# xds100v2.net
KiCad netlist of a schematic drawn in Altium Designer
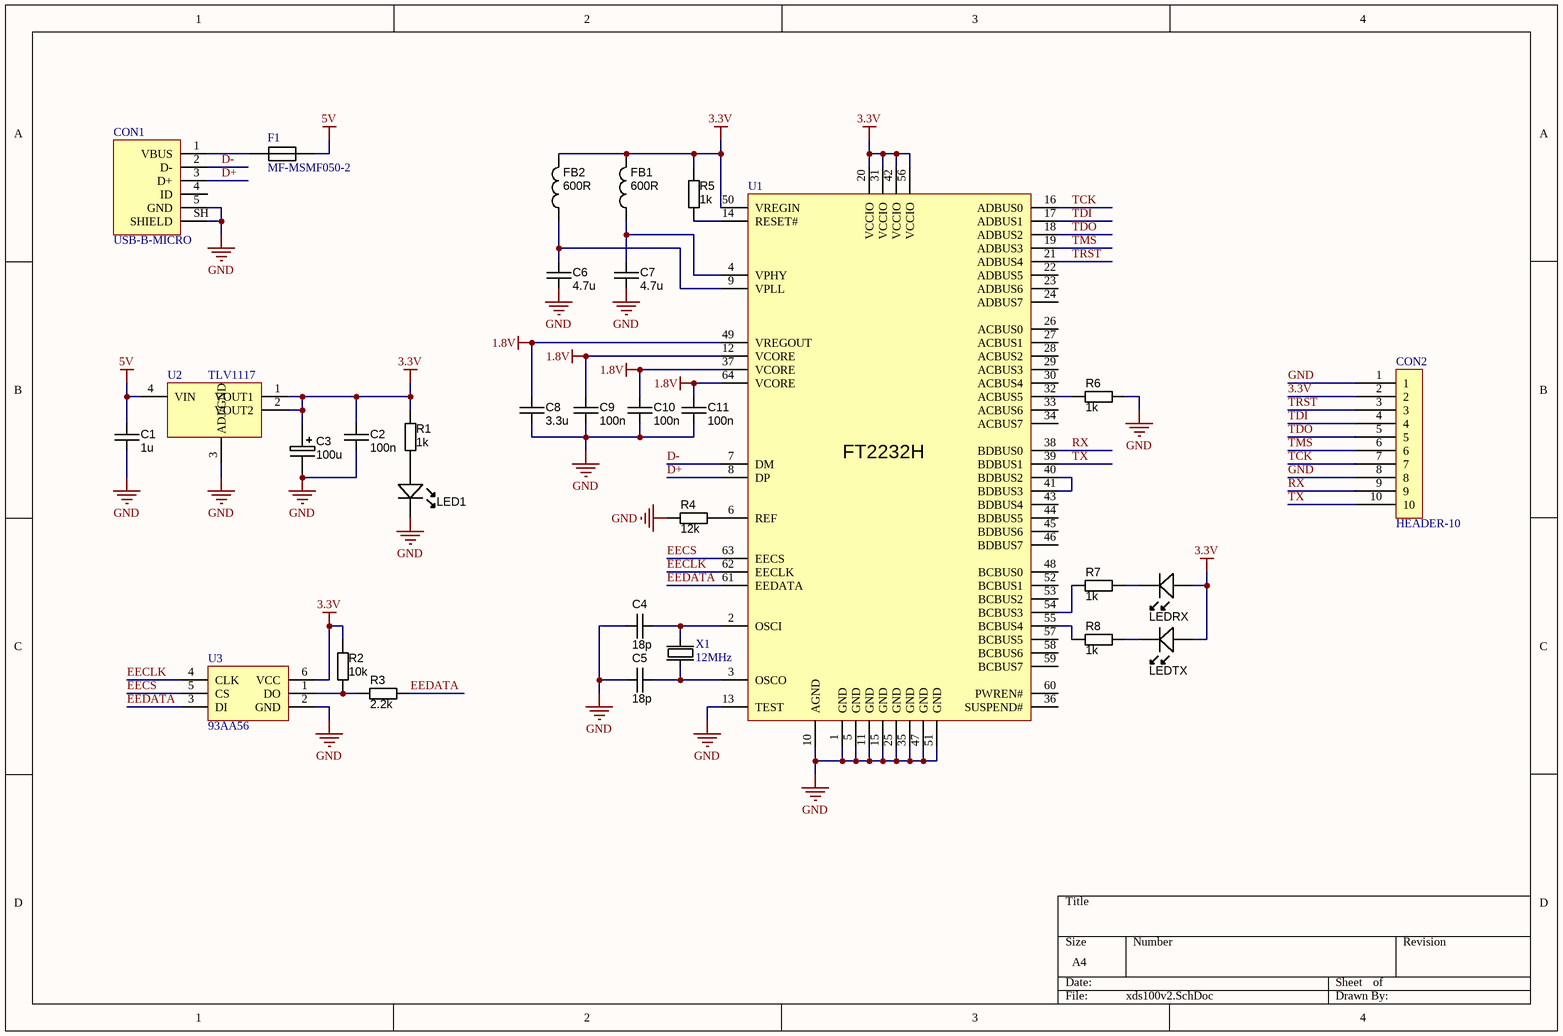
[diagram p0: xds100v2.SchDoc]

(export (version "E")
  (design (tool "Eeschema 10.0.6"))
  (components
    (comp (ref "C1")
      (value "1u")
      (footprint "CAPC1608X90N")
      (description "Capacitor SMD Cer 1uF 10% 16V X7R 0603")
      (fields (field (name "TOLERANCE") "±10%"))
      (libsource (lib "PBL - Capacitors") (part "CAPC_1u_0603_X7R_16V_10%"))
    )
    (comp (ref "C2")
      (value "100n")
      (footprint "CAPC1608X90N")
      (description "Capacitor SMD Cer 1uF 10% 16V X7R 0603")
      (fields (field (name "TOLERANCE") "±10%"))
      (libsource (lib "PBL - Capacitors") (part "CAPC_1u_0603_X7R_16V_10%"))
    )
    (comp (ref "C3")
      (value "100u")
      (footprint "CAPMP3528X210N")
      (description "Capacitor SMD Tantalum 100uF 20% 6.3V 1210")
      (fields (field (name "TOLERANCE") "±20%"))
      (libsource (lib "PBL - Capacitors") (part "CAPT_100u_1210_6V3"))
    )
    (comp (ref "C4")
      (value "18p")
      (footprint "CAPC1608X90N")
      (description "Capacitor SMD Cer 1uF 10% 16V X7R 0603")
      (fields (field (name "TOLERANCE") "±10%"))
      (libsource (lib "PBL - Capacitors") (part "CAPC_1u_0603_X7R_16V_10%"))
    )
    (comp (ref "C5")
      (value "18p")
      (footprint "CAPC1608X90N")
      (description "Capacitor SMD Cer 1uF 10% 16V X7R 0603")
      (fields (field (name "TOLERANCE") "±10%"))
      (libsource (lib "PBL - Capacitors") (part "CAPC_1u_0603_X7R_16V_10%"))
    )
    (comp (ref "C6")
      (value "4.7u")
      (footprint "CAPC1608X90N")
      (description "Capacitor SMD Cer 1uF 10% 16V X7R 0603")
      (fields (field (name "TOLERANCE") "±10%"))
      (libsource (lib "PBL - Capacitors") (part "CAPC_1u_0603_X7R_16V_10%"))
    )
    (comp (ref "C7")
      (value "4.7u")
      (footprint "CAPC1608X90N")
      (description "Capacitor SMD Cer 1uF 10% 16V X7R 0603")
      (fields (field (name "TOLERANCE") "±10%"))
      (libsource (lib "PBL - Capacitors") (part "CAPC_1u_0603_X7R_16V_10%"))
    )
    (comp (ref "C8")
      (value "3.3u")
      (footprint "CAPC1608X90N")
      (description "Capacitor SMD Cer 1uF 10% 16V X7R 0603")
      (fields (field (name "TOLERANCE") "±10%"))
      (libsource (lib "PBL - Capacitors") (part "CAPC_1u_0603_X7R_16V_10%"))
    )
    (comp (ref "C9")
      (value "100n")
      (footprint "CAPC1608X90N")
      (description "Capacitor SMD Cer 1uF 10% 16V X7R 0603")
      (fields (field (name "TOLERANCE") "±10%"))
      (libsource (lib "PBL - Capacitors") (part "CAPC_1u_0603_X7R_16V_10%"))
    )
    (comp (ref "C10")
      (value "100n")
      (footprint "CAPC1608X90N")
      (description "Capacitor SMD Cer 1uF 10% 16V X7R 0603")
      (fields (field (name "TOLERANCE") "±10%"))
      (libsource (lib "PBL - Capacitors") (part "CAPC_1u_0603_X7R_16V_10%"))
    )
    (comp (ref "C11")
      (value "100n")
      (footprint "CAPC1608X90N")
      (description "Capacitor SMD Cer 1uF 10% 16V X7R 0603")
      (fields (field (name "TOLERANCE") "±10%"))
      (libsource (lib "PBL - Capacitors") (part "CAPC_1u_0603_X7R_16V_10%"))
    )
    (comp (ref "CON1")
      (value "USB-B-MICRO")
      (footprint "USB-B-MICRO-FCI-10104110")
      (libsource (lib "connectors") (part "USB-B-MICRO"))
    )
    (comp (ref "CON2")
      (value "HEADER-10")
      (footprint "MICRO-MATCH-10")
      (libsource (lib "connectors") (part "HEADER-10"))
    )
    (comp (ref "F1")
      (value "MF-MSMF050-2")
      (footprint "PTC-1218")
      (libsource (lib "power") (part "MF-MSMF050-2"))
    )
    (comp (ref "FB1")
      (value "600R")
      (footprint "INDC1608N")
      (description "Ferrite bead 120 Ohm at 100 MHz 2A 0603 SMD")
      (libsource (lib "PBL - Inductors") (part "FERRITE_120R-100MHz_0603"))
    )
    (comp (ref "FB2")
      (value "600R")
      (footprint "INDC1608N")
      (description "Ferrite bead 120 Ohm at 100 MHz 2A 0603 SMD")
      (libsource (lib "PBL - Inductors") (part "FERRITE_120R-100MHz_0603"))
    )
    (comp (ref "LED1")
      (value "Green")
      (footprint "LED-0603-GREEN")
      (description "LED 0603 SMD Green 570nm 50mcd 20mA")
      (libsource (lib "PBL - Light Sources") (part "LED_SMD_Green_0603_570nm"))
    )
    (comp (ref "LEDRX")
      (value "Green")
      (footprint "LED-0603-GREEN")
      (description "LED 0603 SMD Green 570nm 50mcd 20mA")
      (libsource (lib "PBL - Light Sources") (part "LED_SMD_Green_0603_570nm"))
    )
    (comp (ref "LEDTX")
      (value "Green")
      (footprint "LED-0603-GREEN")
      (description "LED 0603 SMD Green 570nm 50mcd 20mA")
      (libsource (lib "PBL - Light Sources") (part "LED_SMD_Green_0603_570nm"))
    )
    (comp (ref "R1")
      (value "1k")
      (footprint "RESC1608X55N")
      (description "Resistor SMD chip 1k Ohm 0.1W 1% 0603")
      (fields (field (name "TOLERANCE") "±1%"))
      (libsource (lib "PBL - Resistors") (part "RES_1K_0603_1%"))
    )
    (comp (ref "R2")
      (value "10k")
      (footprint "RESC1608X55N")
      (description "Resistor SMD chip 1k Ohm 0.1W 1% 0603")
      (fields (field (name "TOLERANCE") "±1%"))
      (libsource (lib "PBL - Resistors") (part "RES_1K_0603_1%"))
    )
    (comp (ref "R3")
      (value "2.2k")
      (footprint "RESC1608X55N")
      (description "Resistor SMD chip 1k Ohm 0.1W 1% 0603")
      (fields (field (name "TOLERANCE") "±1%"))
      (libsource (lib "") (part "RES_1K_0603_1%_2"))
    )
    (comp (ref "R4")
      (value "12k")
      (footprint "RESC1608X55N")
      (description "Resistor SMD chip 1k Ohm 0.1W 1% 0603")
      (fields (field (name "TOLERANCE") "±1%"))
      (libsource (lib "") (part "RES_1K_0603_1%_2"))
    )
    (comp (ref "R5")
      (value "1k")
      (footprint "RESC1608X55N")
      (description "Resistor SMD chip 1k Ohm 0.1W 1% 0603")
      (fields (field (name "TOLERANCE") "±1%"))
      (libsource (lib "PBL - Resistors") (part "RES_1K_0603_1%"))
    )
    (comp (ref "R6")
      (value "1k")
      (footprint "RESC1608X55N")
      (description "Resistor SMD chip 1k Ohm 0.1W 1% 0603")
      (fields (field (name "TOLERANCE") "±1%"))
      (libsource (lib "") (part "RES_1K_0603_1%_1"))
    )
    (comp (ref "R7")
      (value "1k")
      (footprint "RESC1608X55N")
      (description "Resistor SMD chip 1k Ohm 0.1W 1% 0603")
      (fields (field (name "TOLERANCE") "±1%"))
      (libsource (lib "") (part "RES_1K_0603_1%_1"))
    )
    (comp (ref "R8")
      (value "1k")
      (footprint "RESC1608X55N")
      (description "Resistor SMD chip 1k Ohm 0.1W 1% 0603")
      (fields (field (name "TOLERANCE") "±1%"))
      (libsource (lib "") (part "RES_1K_0603_1%_1"))
    )
    (comp (ref "U1")
      (value "FT2232H")
      (footprint "TSQFP50P1200X1200X160-64N")
      (libsource (lib "ftdi_chip") (part "FT2232H"))
    )
    (comp (ref "U2")
      (value "TLV1117")
      (footprint "SOT223")
      (libsource (lib "texas_instruments") (part "TLV1117"))
    )
    (comp (ref "U3")
      (value "93AA56")
      (footprint "TSOT-23-6")
      (description "EEPROM")
      (libsource (lib "digital") (part "93AA56"))
    )
    (comp (ref "X1") (value "12MHz") (footprint "XTAL-5x3.2") (libsource (lib "misc") (part "XTAL_5x3.2")))
  )
  (nets
    (net (code "1") (name "/D+") (class "Default")
      (node (ref "CON1") (pin "3") (pinfunction "D+_3") (pintype "passive"))
      (node (ref "U1") (pin "8") (pinfunction "DP_8") (pintype "passive"))
    )
    (net (code "2") (name "/D-") (class "Default")
      (node (ref "CON1") (pin "2") (pinfunction "D-_2") (pintype "passive"))
      (node (ref "U1") (pin "7") (pinfunction "DM_7") (pintype "passive"))
    )
    (net (code "3") (name "/EECLK") (class "Default")
      (node (ref "U1") (pin "62") (pinfunction "EECLK_62") (pintype "passive"))
      (node (ref "U3") (pin "4") (pinfunction "CLK_4") (pintype "passive"))
    )
    (net (code "4") (name "/EECS") (class "Default")
      (node (ref "U1") (pin "63") (pinfunction "EECS_63") (pintype "passive"))
      (node (ref "U3") (pin "5") (pinfunction "CS_5") (pintype "passive"))
    )
    (net (code "5") (name "/EEDATA") (class "Default")
      (node (ref "R3") (pin "1") (pinfunction "1_1") (pintype "passive"))
      (node (ref "U1") (pin "61") (pinfunction "EEDATA_61") (pintype "passive"))
      (node (ref "U3") (pin "3") (pinfunction "DI_3") (pintype "passive"))
    )
    (net (code "6") (name "/RX") (class "Default")
      (node (ref "CON2") (pin "9") (pinfunction "9_9") (pintype "passive"))
      (node (ref "U1") (pin "38") (pinfunction "BDBUS0_38") (pintype "passive"))
    )
    (net (code "7") (name "/TCK") (class "Default")
      (node (ref "CON2") (pin "7") (pinfunction "7_7") (pintype "passive"))
      (node (ref "U1") (pin "16") (pinfunction "ADBUS0_16") (pintype "passive"))
    )
    (net (code "8") (name "/TDI") (class "Default")
      (node (ref "CON2") (pin "4") (pinfunction "4_4") (pintype "passive"))
      (node (ref "U1") (pin "17") (pinfunction "ADBUS1_17") (pintype "passive"))
    )
    (net (code "9") (name "/TDO") (class "Default")
      (node (ref "CON2") (pin "5") (pinfunction "5_5") (pintype "passive"))
      (node (ref "U1") (pin "18") (pinfunction "ADBUS2_18") (pintype "passive"))
    )
    (net (code "10") (name "/TMS") (class "Default")
      (node (ref "CON2") (pin "6") (pinfunction "6_6") (pintype "passive"))
      (node (ref "U1") (pin "19") (pinfunction "ADBUS3_19") (pintype "passive"))
    )
    (net (code "11") (name "/TRST") (class "Default")
      (node (ref "CON2") (pin "3") (pinfunction "3_3") (pintype "passive"))
      (node (ref "U1") (pin "21") (pinfunction "ADBUS4_21") (pintype "passive"))
    )
    (net (code "12") (name "/TX") (class "Default")
      (node (ref "CON2") (pin "10") (pinfunction "10_10") (pintype "passive"))
      (node (ref "U1") (pin "39") (pinfunction "BDBUS1_39") (pintype "passive"))
    )
    (net (code "13") (name "1.8V") (class "Default")
      (node (ref "C10") (pin "2") (pintype "passive"))
      (node (ref "C11") (pin "2") (pintype "passive"))
      (node (ref "C8") (pin "1") (pintype "passive"))
      (node (ref "C9") (pin "2") (pintype "passive"))
      (node (ref "U1") (pin "12") (pinfunction "VCORE_12") (pintype "passive"))
      (node (ref "U1") (pin "37") (pinfunction "VCORE_37") (pintype "passive"))
      (node (ref "U1") (pin "49") (pinfunction "VREGOUT_49") (pintype "passive"))
      (node (ref "U1") (pin "64") (pinfunction "VCORE_64") (pintype "passive"))
    )
    (net (code "14") (name "3.3V") (class "Default")
      (node (ref "C2") (pin "1") (pintype "passive"))
      (node (ref "C3") (pin "1") (pintype "passive"))
      (node (ref "CON2") (pin "2") (pinfunction "2_2") (pintype "passive"))
      (node (ref "FB1") (pin "2") (pinfunction "2_2") (pintype "passive"))
      (node (ref "FB2") (pin "2") (pinfunction "2_2") (pintype "passive"))
      (node (ref "LEDRX") (pin "A") (pinfunction "A_A") (pintype "passive"))
      (node (ref "LEDTX") (pin "A") (pinfunction "A_A") (pintype "passive"))
      (node (ref "R1") (pin "2") (pinfunction "2_2") (pintype "passive"))
      (node (ref "R2") (pin "2") (pinfunction "2_2") (pintype "passive"))
      (node (ref "R5") (pin "2") (pinfunction "2_2") (pintype "passive"))
      (node (ref "U1") (pin "20") (pinfunction "VCCIO_20") (pintype "passive"))
      (node (ref "U1") (pin "31") (pinfunction "VCCIO_31") (pintype "passive"))
      (node (ref "U1") (pin "42") (pinfunction "VCCIO_42") (pintype "passive"))
      (node (ref "U1") (pin "50") (pinfunction "VREGIN_50") (pintype "passive"))
      (node (ref "U1") (pin "56") (pinfunction "VCCIO_56") (pintype "passive"))
      (node (ref "U2") (pin "1") (pinfunction "VOUT1_1") (pintype "passive"))
      (node (ref "U2") (pin "2") (pinfunction "VOUT2_2") (pintype "passive"))
      (node (ref "U3") (pin "6") (pinfunction "VCC_6") (pintype "passive"))
    )
    (net (code "15") (name "5V") (class "Default")
      (node (ref "C1") (pin "2") (pintype "passive"))
      (node (ref "F1") (pin "22") (pinfunction "2_22") (pintype "passive"))
      (node (ref "U2") (pin "4") (pinfunction "VIN_4") (pintype "passive"))
    )
    (net (code "16") (name "GND") (class "Default")
      (node (ref "C1") (pin "1") (pintype "passive"))
      (node (ref "C10") (pin "1") (pintype "passive"))
      (node (ref "C11") (pin "1") (pintype "passive"))
      (node (ref "C2") (pin "2") (pintype "passive"))
      (node (ref "C3") (pin "2") (pintype "passive"))
      (node (ref "C4") (pin "2") (pintype "passive"))
      (node (ref "C5") (pin "2") (pintype "passive"))
      (node (ref "C6") (pin "2") (pintype "passive"))
      (node (ref "C7") (pin "1") (pintype "passive"))
      (node (ref "C8") (pin "2") (pintype "passive"))
      (node (ref "C9") (pin "1") (pintype "passive"))
      (node (ref "CON1") (pin "5") (pinfunction "GND_5") (pintype "passive"))
      (node (ref "CON1") (pin "SH") (pinfunction "SHIELD_SH") (pintype "passive"))
      (node (ref "CON2") (pin "1") (pinfunction "1_1") (pintype "passive"))
      (node (ref "CON2") (pin "8") (pinfunction "8_8") (pintype "passive"))
      (node (ref "LED1") (pin "K") (pinfunction "K_K") (pintype "passive"))
      (node (ref "R4") (pin "2") (pinfunction "2_2") (pintype "passive"))
      (node (ref "R6") (pin "2") (pinfunction "2_2") (pintype "passive"))
      (node (ref "U1") (pin "1") (pinfunction "GND_1") (pintype "passive"))
      (node (ref "U1") (pin "10") (pinfunction "AGND_10") (pintype "passive"))
      (node (ref "U1") (pin "11") (pinfunction "GND_11") (pintype "passive"))
      (node (ref "U1") (pin "13") (pinfunction "TEST_13") (pintype "passive"))
      (node (ref "U1") (pin "15") (pinfunction "GND_15") (pintype "passive"))
      (node (ref "U1") (pin "25") (pinfunction "GND_25") (pintype "passive"))
      (node (ref "U1") (pin "35") (pinfunction "GND_35") (pintype "passive"))
      (node (ref "U1") (pin "47") (pinfunction "GND_47") (pintype "passive"))
      (node (ref "U1") (pin "5") (pinfunction "GND_5") (pintype "passive"))
      (node (ref "U1") (pin "51") (pinfunction "GND_51") (pintype "passive"))
      (node (ref "U2") (pin "3") (pinfunction "ADJ/GND_3") (pintype "passive"))
      (node (ref "U3") (pin "2") (pinfunction "GND_2") (pintype "passive"))
    )
    (net (code "17") (name "Net-(CON1-VBUS)") (class "Default")
      (node (ref "CON1") (pin "1") (pinfunction "VBUS_1") (pintype "passive"))
      (node (ref "F1") (pin "21") (pinfunction "1_21") (pintype "passive"))
    )
    (net (code "18") (name "Net-(LED1-PadA)") (class "Default")
      (node (ref "LED1") (pin "A") (pinfunction "A_A") (pintype "passive"))
      (node (ref "R1") (pin "1") (pinfunction "1_1") (pintype "passive"))
    )
    (net (code "19") (name "Net-(LEDRX-PadK)") (class "Default")
      (node (ref "LEDRX") (pin "K") (pinfunction "K_K") (pintype "passive"))
      (node (ref "R7") (pin "2") (pinfunction "2_2") (pintype "passive"))
    )
    (net (code "20") (name "Net-(LEDTX-PadK)") (class "Default")
      (node (ref "LEDTX") (pin "K") (pinfunction "K_K") (pintype "passive"))
      (node (ref "R8") (pin "2") (pinfunction "2_2") (pintype "passive"))
    )
    (net (code "21") (name "Net-(U1-ACBUS5)") (class "Default")
      (node (ref "R6") (pin "1") (pinfunction "1_1") (pintype "passive"))
      (node (ref "U1") (pin "32") (pinfunction "ACBUS5_32") (pintype "passive"))
    )
    (net (code "22") (name "Net-(U1-BCBUS3)") (class "Default")
      (node (ref "R7") (pin "1") (pinfunction "1_1") (pintype "passive"))
      (node (ref "U1") (pin "54") (pinfunction "BCBUS3_54") (pintype "passive"))
    )
    (net (code "23") (name "Net-(U1-BCBUS4)") (class "Default")
      (node (ref "R8") (pin "1") (pinfunction "1_1") (pintype "passive"))
      (node (ref "U1") (pin "55") (pinfunction "BCBUS4_55") (pintype "passive"))
    )
    (net (code "24") (name "Net-(U1-BDBUS2)") (class "Default")
      (node (ref "U1") (pin "40") (pinfunction "BDBUS2_40") (pintype "passive"))
      (node (ref "U1") (pin "41") (pinfunction "BDBUS3_41") (pintype "passive"))
    )
    (net (code "25") (name "Net-(U1-OSCI)") (class "Default")
      (node (ref "C4") (pin "1") (pintype "passive"))
      (node (ref "U1") (pin "2") (pinfunction "OSCI_2") (pintype "passive"))
      (node (ref "X1") (pin "1") (pinfunction "1_1") (pintype "passive"))
    )
    (net (code "26") (name "Net-(U1-OSCO)") (class "Default")
      (node (ref "C5") (pin "1") (pintype "passive"))
      (node (ref "U1") (pin "3") (pinfunction "OSCO_3") (pintype "passive"))
      (node (ref "X1") (pin "2") (pinfunction "2_2") (pintype "passive"))
    )
    (net (code "27") (name "Net-(U1-REF)") (class "Default")
      (node (ref "R4") (pin "1") (pinfunction "1_1") (pintype "passive"))
      (node (ref "U1") (pin "6") (pinfunction "REF_6") (pintype "passive"))
    )
    (net (code "28") (name "Net-(U1-RESET#)") (class "Default")
      (node (ref "R5") (pin "1") (pinfunction "1_1") (pintype "passive"))
      (node (ref "U1") (pin "14") (pinfunction "RESET#_14") (pintype "passive"))
    )
    (net (code "29") (name "Net-(U1-VPHY)") (class "Default")
      (node (ref "C7") (pin "2") (pintype "passive"))
      (node (ref "FB1") (pin "1") (pinfunction "1_1") (pintype "passive"))
      (node (ref "U1") (pin "4") (pinfunction "VPHY_4") (pintype "passive"))
    )
    (net (code "30") (name "Net-(U1-VPLL)") (class "Default")
      (node (ref "C6") (pin "1") (pintype "passive"))
      (node (ref "FB2") (pin "1") (pinfunction "1_1") (pintype "passive"))
      (node (ref "U1") (pin "9") (pinfunction "VPLL_9") (pintype "passive"))
    )
    (net (code "31") (name "Net-(U3-DO)") (class "Default")
      (node (ref "R2") (pin "1") (pinfunction "1_1") (pintype "passive"))
      (node (ref "R3") (pin "2") (pinfunction "2_2") (pintype "passive"))
      (node (ref "U3") (pin "1") (pinfunction "DO_1") (pintype "passive"))
    )
    (net (code "32") (name "unconnected-(CON1-ID-Pad4)") (class "Default")
      (node (ref "CON1") (pin "4") (pinfunction "ID_4") (pintype "passive"))
    )
    (net (code "33") (name "unconnected-(U1-ACBUS0-Pad26)") (class "Default")
      (node (ref "U1") (pin "26") (pinfunction "ACBUS0_26") (pintype "passive"))
    )
    (net (code "34") (name "unconnected-(U1-ACBUS1-Pad27)") (class "Default")
      (node (ref "U1") (pin "27") (pinfunction "ACBUS1_27") (pintype "passive"))
    )
    (net (code "35") (name "unconnected-(U1-ACBUS2-Pad28)") (class "Default")
      (node (ref "U1") (pin "28") (pinfunction "ACBUS2_28") (pintype "passive"))
    )
    (net (code "36") (name "unconnected-(U1-ACBUS3-Pad29)") (class "Default")
      (node (ref "U1") (pin "29") (pinfunction "ACBUS3_29") (pintype "passive"))
    )
    (net (code "37") (name "unconnected-(U1-ACBUS4-Pad30)") (class "Default")
      (node (ref "U1") (pin "30") (pinfunction "ACBUS4_30") (pintype "passive"))
    )
    (net (code "38") (name "unconnected-(U1-ACBUS6-Pad33)") (class "Default")
      (node (ref "U1") (pin "33") (pinfunction "ACBUS6_33") (pintype "passive"))
    )
    (net (code "39") (name "unconnected-(U1-ACBUS7-Pad34)") (class "Default")
      (node (ref "U1") (pin "34") (pinfunction "ACBUS7_34") (pintype "passive"))
    )
    (net (code "40") (name "unconnected-(U1-ADBUS5-Pad22)") (class "Default")
      (node (ref "U1") (pin "22") (pinfunction "ADBUS5_22") (pintype "passive"))
    )
    (net (code "41") (name "unconnected-(U1-ADBUS6-Pad23)") (class "Default")
      (node (ref "U1") (pin "23") (pinfunction "ADBUS6_23") (pintype "passive"))
    )
    (net (code "42") (name "unconnected-(U1-ADBUS7-Pad24)") (class "Default")
      (node (ref "U1") (pin "24") (pinfunction "ADBUS7_24") (pintype "passive"))
    )
    (net (code "43") (name "unconnected-(U1-BCBUS0-Pad48)") (class "Default")
      (node (ref "U1") (pin "48") (pinfunction "BCBUS0_48") (pintype "passive"))
    )
    (net (code "44") (name "unconnected-(U1-BCBUS1-Pad52)") (class "Default")
      (node (ref "U1") (pin "52") (pinfunction "BCBUS1_52") (pintype "passive"))
    )
    (net (code "45") (name "unconnected-(U1-BCBUS2-Pad53)") (class "Default")
      (node (ref "U1") (pin "53") (pinfunction "BCBUS2_53") (pintype "passive"))
    )
    (net (code "46") (name "unconnected-(U1-BCBUS5-Pad57)") (class "Default")
      (node (ref "U1") (pin "57") (pinfunction "BCBUS5_57") (pintype "passive"))
    )
    (net (code "47") (name "unconnected-(U1-BCBUS6-Pad58)") (class "Default")
      (node (ref "U1") (pin "58") (pinfunction "BCBUS6_58") (pintype "passive"))
    )
    (net (code "48") (name "unconnected-(U1-BCBUS7-Pad59)") (class "Default")
      (node (ref "U1") (pin "59") (pinfunction "BCBUS7_59") (pintype "passive"))
    )
    (net (code "49") (name "unconnected-(U1-BDBUS4-Pad43)") (class "Default")
      (node (ref "U1") (pin "43") (pinfunction "BDBUS4_43") (pintype "passive"))
    )
    (net (code "50") (name "unconnected-(U1-BDBUS5-Pad44)") (class "Default")
      (node (ref "U1") (pin "44") (pinfunction "BDBUS5_44") (pintype "passive"))
    )
    (net (code "51") (name "unconnected-(U1-BDBUS6-Pad45)") (class "Default")
      (node (ref "U1") (pin "45") (pinfunction "BDBUS6_45") (pintype "passive"))
    )
    (net (code "52") (name "unconnected-(U1-BDBUS7-Pad46)") (class "Default")
      (node (ref "U1") (pin "46") (pinfunction "BDBUS7_46") (pintype "passive"))
    )
    (net (code "53") (name "unconnected-(U1-PWREN#-Pad60)") (class "Default")
      (node (ref "U1") (pin "60") (pinfunction "PWREN#_60") (pintype "passive"))
    )
    (net (code "54") (name "unconnected-(U1-SUSPEND#-Pad36)") (class "Default")
      (node (ref "U1") (pin "36") (pinfunction "SUSPEND#_36") (pintype "passive"))
    )
  )
)
